# LPC2LCD.net
KiCad netlist of a schematic drawn in EAGLE
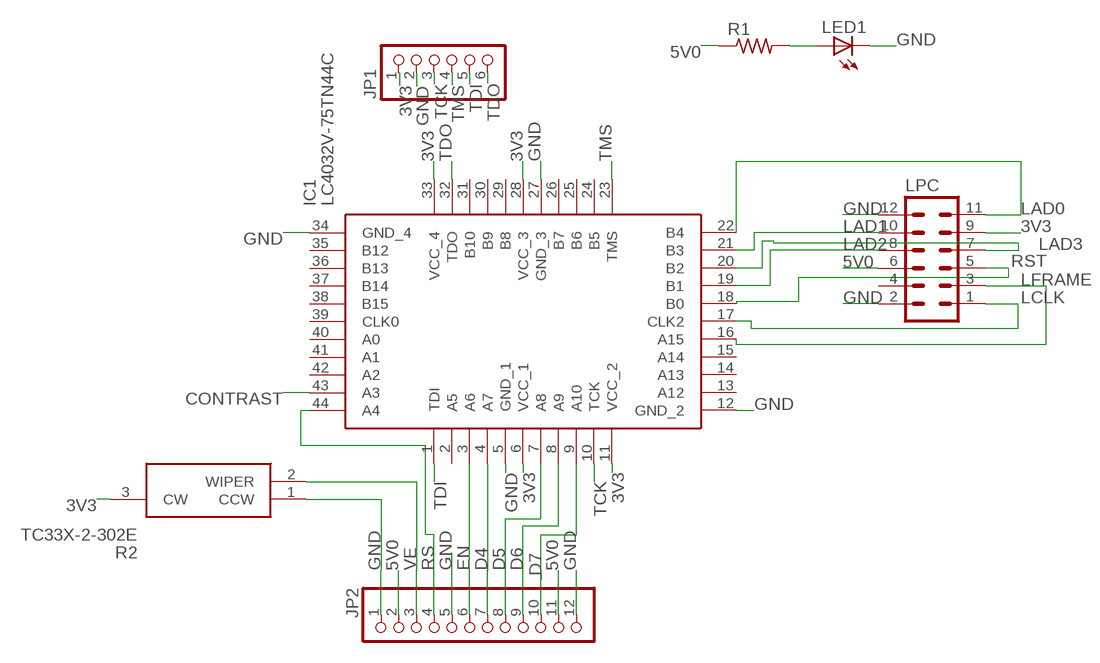
[diagram p0: schematic, sheet 1]

(export (version "E")
  (design (tool "Eeschema 10.0.6"))
  (components
    (comp (ref "IC1")
      (value "LC4032V-75TN44C")
      (footprint "eagle-import:QFP80P1200X1200X120-44N")
      (fields (field (name "MOUSER_PART_NUMBER") "842-LC4032V75TN44C"))
      (libsource (lib "eagle-import") (part "LC4032V-75TN44C"))
    )
    (comp (ref "JP1")
      (value "PINHD-1X6B")
      (footprint "eagle-import:1X06-BIG")
      (libsource (lib "eagle-import") (part "PINHD-1X6B"))
    )
    (comp (ref "JP2")
      (value "PINHD-1X12")
      (footprint "eagle-import:1X12")
      (libsource (lib "eagle-import") (part "PINHD-1X12"))
    )
    (comp (ref "LED1")
      (value "LEDCHIPLED_0805")
      (footprint "eagle-import:CHIPLED_0805")
      (libsource (lib "eagle-import") (part "LEDCHIPLED_0805"))
    )
    (comp (ref "LPC")
      (value "MA06-2")
      (footprint "eagle-import:MA06-2")
      (libsource (lib "eagle-import") (part "MA06-2"))
    )
    (comp (ref "R1")
      (value "R-US_R0805")
      (footprint "eagle-import:R0805")
      (libsource (lib "eagle-import") (part "R-US_R0805"))
    )
    (comp (ref "R2")
      (value "TC33X-2-302E")
      (footprint "eagle-import:TC33X-2")
      (fields (field (name "MOUSER_PART_NUMBER") "652-TC33X-2-302E"))
      (libsource (lib "eagle-import") (part "TC33X-2-302E"))
    )
  )
  (nets
    (net (code "1") (name "/3V3") (class "Default")
      (node (ref "IC1") (pin "11") (pinfunction "VCC_2_11") (pintype "power_in"))
      (node (ref "IC1") (pin "28") (pinfunction "VCC_3_28") (pintype "power_in"))
      (node (ref "IC1") (pin "33") (pinfunction "VCC_4_33") (pintype "power_in"))
      (node (ref "IC1") (pin "6") (pinfunction "VCC_1_6") (pintype "power_in"))
      (node (ref "JP1") (pin "1") (pinfunction "1_1") (pintype "passive"))
      (node (ref "LPC") (pin "9") (pinfunction "9_9") (pintype "passive"))
      (node (ref "R2") (pin "3") (pinfunction "CW_3") (pintype "bidirectional"))
    )
    (net (code "2") (name "/5V0") (class "Default")
      (node (ref "JP2") (pin "11") (pinfunction "11_11") (pintype "passive"))
      (node (ref "JP2") (pin "2") (pinfunction "2_2") (pintype "passive"))
      (node (ref "LPC") (pin "6") (pinfunction "6_6") (pintype "passive"))
      (node (ref "R1") (pin "1") (pinfunction "1_1") (pintype "passive"))
    )
    (net (code "3") (name "/CONTRAST") (class "Default")
      (node (ref "IC1") (pin "43") (pinfunction "A3_43") (pintype "bidirectional"))
    )
    (net (code "4") (name "/D4") (class "Default")
      (node (ref "IC1") (pin "4") (pinfunction "A7_4") (pintype "bidirectional"))
      (node (ref "JP2") (pin "7") (pinfunction "7_7") (pintype "passive"))
    )
    (net (code "5") (name "/D5") (class "Default")
      (node (ref "IC1") (pin "7") (pinfunction "A8_7") (pintype "bidirectional"))
      (node (ref "JP2") (pin "8") (pinfunction "8_8") (pintype "passive"))
    )
    (net (code "6") (name "/D6") (class "Default")
      (node (ref "IC1") (pin "8") (pinfunction "A9_8") (pintype "bidirectional"))
      (node (ref "JP2") (pin "9") (pinfunction "9_9") (pintype "passive"))
    )
    (net (code "7") (name "/D7") (class "Default")
      (node (ref "IC1") (pin "9") (pinfunction "A10_9") (pintype "bidirectional"))
      (node (ref "JP2") (pin "10") (pinfunction "10_10") (pintype "passive"))
    )
    (net (code "8") (name "/EN") (class "Default")
      (node (ref "IC1") (pin "3") (pinfunction "A6_3") (pintype "bidirectional"))
      (node (ref "JP2") (pin "6") (pinfunction "6_6") (pintype "passive"))
    )
    (net (code "9") (name "/GND") (class "Default")
      (node (ref "IC1") (pin "12") (pinfunction "GND_2_12") (pintype "power_in"))
      (node (ref "IC1") (pin "27") (pinfunction "GND_3_27") (pintype "power_in"))
      (node (ref "IC1") (pin "34") (pinfunction "GND_4_34") (pintype "power_in"))
      (node (ref "IC1") (pin "5") (pinfunction "GND_1_5") (pintype "power_in"))
      (node (ref "JP1") (pin "2") (pinfunction "2_2") (pintype "passive"))
      (node (ref "JP2") (pin "1") (pinfunction "1_1") (pintype "passive"))
      (node (ref "JP2") (pin "12") (pinfunction "12_12") (pintype "passive"))
      (node (ref "JP2") (pin "5") (pinfunction "5_5") (pintype "passive"))
      (node (ref "LED1") (pin "C") (pinfunction "C_C") (pintype "passive"))
      (node (ref "LPC") (pin "12") (pinfunction "12_12") (pintype "passive"))
      (node (ref "LPC") (pin "2") (pinfunction "2_2") (pintype "passive"))
      (node (ref "R2") (pin "1") (pinfunction "CCW_1") (pintype "bidirectional"))
    )
    (net (code "10") (name "/LAD0") (class "Default")
      (node (ref "IC1") (pin "22") (pinfunction "B4_22") (pintype "bidirectional"))
      (node (ref "LPC") (pin "11") (pinfunction "11_11") (pintype "passive"))
    )
    (net (code "11") (name "/LAD1") (class "Default")
      (node (ref "IC1") (pin "21") (pinfunction "B3_21") (pintype "bidirectional"))
      (node (ref "LPC") (pin "10") (pinfunction "10_10") (pintype "passive"))
    )
    (net (code "12") (name "/LAD2") (class "Default")
      (node (ref "IC1") (pin "19") (pinfunction "B1_19") (pintype "bidirectional"))
      (node (ref "LPC") (pin "8") (pinfunction "8_8") (pintype "passive"))
    )
    (net (code "13") (name "/LAD3") (class "Default")
      (node (ref "IC1") (pin "20") (pinfunction "B2_20") (pintype "bidirectional"))
      (node (ref "LPC") (pin "7") (pinfunction "7_7") (pintype "passive"))
    )
    (net (code "14") (name "/LCLK") (class "Default")
      (node (ref "IC1") (pin "17") (pinfunction "CLK2_17") (pintype "input"))
      (node (ref "LPC") (pin "1") (pinfunction "1_1") (pintype "passive"))
    )
    (net (code "15") (name "/LFRAME") (class "Default")
      (node (ref "IC1") (pin "16") (pinfunction "A15_16") (pintype "bidirectional"))
      (node (ref "LPC") (pin "3") (pinfunction "3_3") (pintype "passive"))
    )
    (net (code "16") (name "/RS") (class "Default")
      (node (ref "IC1") (pin "44") (pinfunction "A4_44") (pintype "bidirectional"))
      (node (ref "JP2") (pin "4") (pinfunction "4_4") (pintype "passive"))
    )
    (net (code "17") (name "/RST") (class "Default")
      (node (ref "IC1") (pin "18") (pinfunction "B0_18") (pintype "bidirectional"))
      (node (ref "LPC") (pin "5") (pinfunction "5_5") (pintype "passive"))
    )
    (net (code "18") (name "/TCK") (class "Default")
      (node (ref "IC1") (pin "10") (pinfunction "TCK_10") (pintype "input"))
      (node (ref "JP1") (pin "3") (pinfunction "3_3") (pintype "passive"))
    )
    (net (code "19") (name "/TDI") (class "Default")
      (node (ref "IC1") (pin "1") (pinfunction "TDI_1") (pintype "input"))
      (node (ref "JP1") (pin "5") (pinfunction "5_5") (pintype "passive"))
    )
    (net (code "20") (name "/TDO") (class "Default")
      (node (ref "IC1") (pin "32") (pinfunction "TDO_32") (pintype "output"))
      (node (ref "JP1") (pin "6") (pinfunction "6_6") (pintype "passive"))
    )
    (net (code "21") (name "/TMS") (class "Default")
      (node (ref "IC1") (pin "23") (pinfunction "TMS_23") (pintype "input"))
      (node (ref "JP1") (pin "4") (pinfunction "4_4") (pintype "passive"))
    )
    (net (code "22") (name "/VE") (class "Default")
      (node (ref "JP2") (pin "3") (pinfunction "3_3") (pintype "passive"))
      (node (ref "R2") (pin "2") (pinfunction "WIPER_2") (pintype "bidirectional"))
    )
    (net (code "23") (name "Net-(LED1-PadA)") (class "Default")
      (node (ref "LED1") (pin "A") (pinfunction "A_A") (pintype "passive"))
      (node (ref "R1") (pin "2") (pinfunction "2_2") (pintype "passive"))
    )
    (net (code "24") (name "unconnected-(IC1-A0-Pad40)") (class "Default")
      (node (ref "IC1") (pin "40") (pinfunction "A0_40") (pintype "bidirectional"))
    )
    (net (code "25") (name "unconnected-(IC1-A1-Pad41)") (class "Default")
      (node (ref "IC1") (pin "41") (pinfunction "A1_41") (pintype "bidirectional"))
    )
    (net (code "26") (name "unconnected-(IC1-A2-Pad42)") (class "Default")
      (node (ref "IC1") (pin "42") (pinfunction "A2_42") (pintype "bidirectional"))
    )
    (net (code "27") (name "unconnected-(IC1-A5-Pad2)") (class "Default")
      (node (ref "IC1") (pin "2") (pinfunction "A5_2") (pintype "bidirectional"))
    )
    (net (code "28") (name "unconnected-(IC1-A12-Pad13)") (class "Default")
      (node (ref "IC1") (pin "13") (pinfunction "A12_13") (pintype "bidirectional"))
    )
    (net (code "29") (name "unconnected-(IC1-A13-Pad14)") (class "Default")
      (node (ref "IC1") (pin "14") (pinfunction "A13_14") (pintype "bidirectional"))
    )
    (net (code "30") (name "unconnected-(IC1-A14-Pad15)") (class "Default")
      (node (ref "IC1") (pin "15") (pinfunction "A14_15") (pintype "bidirectional"))
    )
    (net (code "31") (name "unconnected-(IC1-B5-Pad24)") (class "Default")
      (node (ref "IC1") (pin "24") (pinfunction "B5_24") (pintype "bidirectional"))
    )
    (net (code "32") (name "unconnected-(IC1-B6-Pad25)") (class "Default")
      (node (ref "IC1") (pin "25") (pinfunction "B6_25") (pintype "bidirectional"))
    )
    (net (code "33") (name "unconnected-(IC1-B7-Pad26)") (class "Default")
      (node (ref "IC1") (pin "26") (pinfunction "B7_26") (pintype "bidirectional"))
    )
    (net (code "34") (name "unconnected-(IC1-B8-Pad29)") (class "Default")
      (node (ref "IC1") (pin "29") (pinfunction "B8_29") (pintype "bidirectional"))
    )
    (net (code "35") (name "unconnected-(IC1-B9-Pad30)") (class "Default")
      (node (ref "IC1") (pin "30") (pinfunction "B9_30") (pintype "bidirectional"))
    )
    (net (code "36") (name "unconnected-(IC1-B10-Pad31)") (class "Default")
      (node (ref "IC1") (pin "31") (pinfunction "B10_31") (pintype "bidirectional"))
    )
    (net (code "37") (name "unconnected-(IC1-B12-Pad35)") (class "Default")
      (node (ref "IC1") (pin "35") (pinfunction "B12_35") (pintype "bidirectional"))
    )
    (net (code "38") (name "unconnected-(IC1-B13-Pad36)") (class "Default")
      (node (ref "IC1") (pin "36") (pinfunction "B13_36") (pintype "bidirectional"))
    )
    (net (code "39") (name "unconnected-(IC1-B14-Pad37)") (class "Default")
      (node (ref "IC1") (pin "37") (pinfunction "B14_37") (pintype "bidirectional"))
    )
    (net (code "40") (name "unconnected-(IC1-B15-Pad38)") (class "Default")
      (node (ref "IC1") (pin "38") (pinfunction "B15_38") (pintype "bidirectional"))
    )
    (net (code "41") (name "unconnected-(IC1-CLK0-Pad39)") (class "Default")
      (node (ref "IC1") (pin "39") (pinfunction "CLK0_39") (pintype "input"))
    )
    (net (code "42") (name "unconnected-(LPC-Pad4)") (class "Default")
      (node (ref "LPC") (pin "4") (pinfunction "4_4") (pintype "passive"))
    )
  )
)
